# node24-bank.net
KiCad netlist of a schematic drawn in Altium Designer
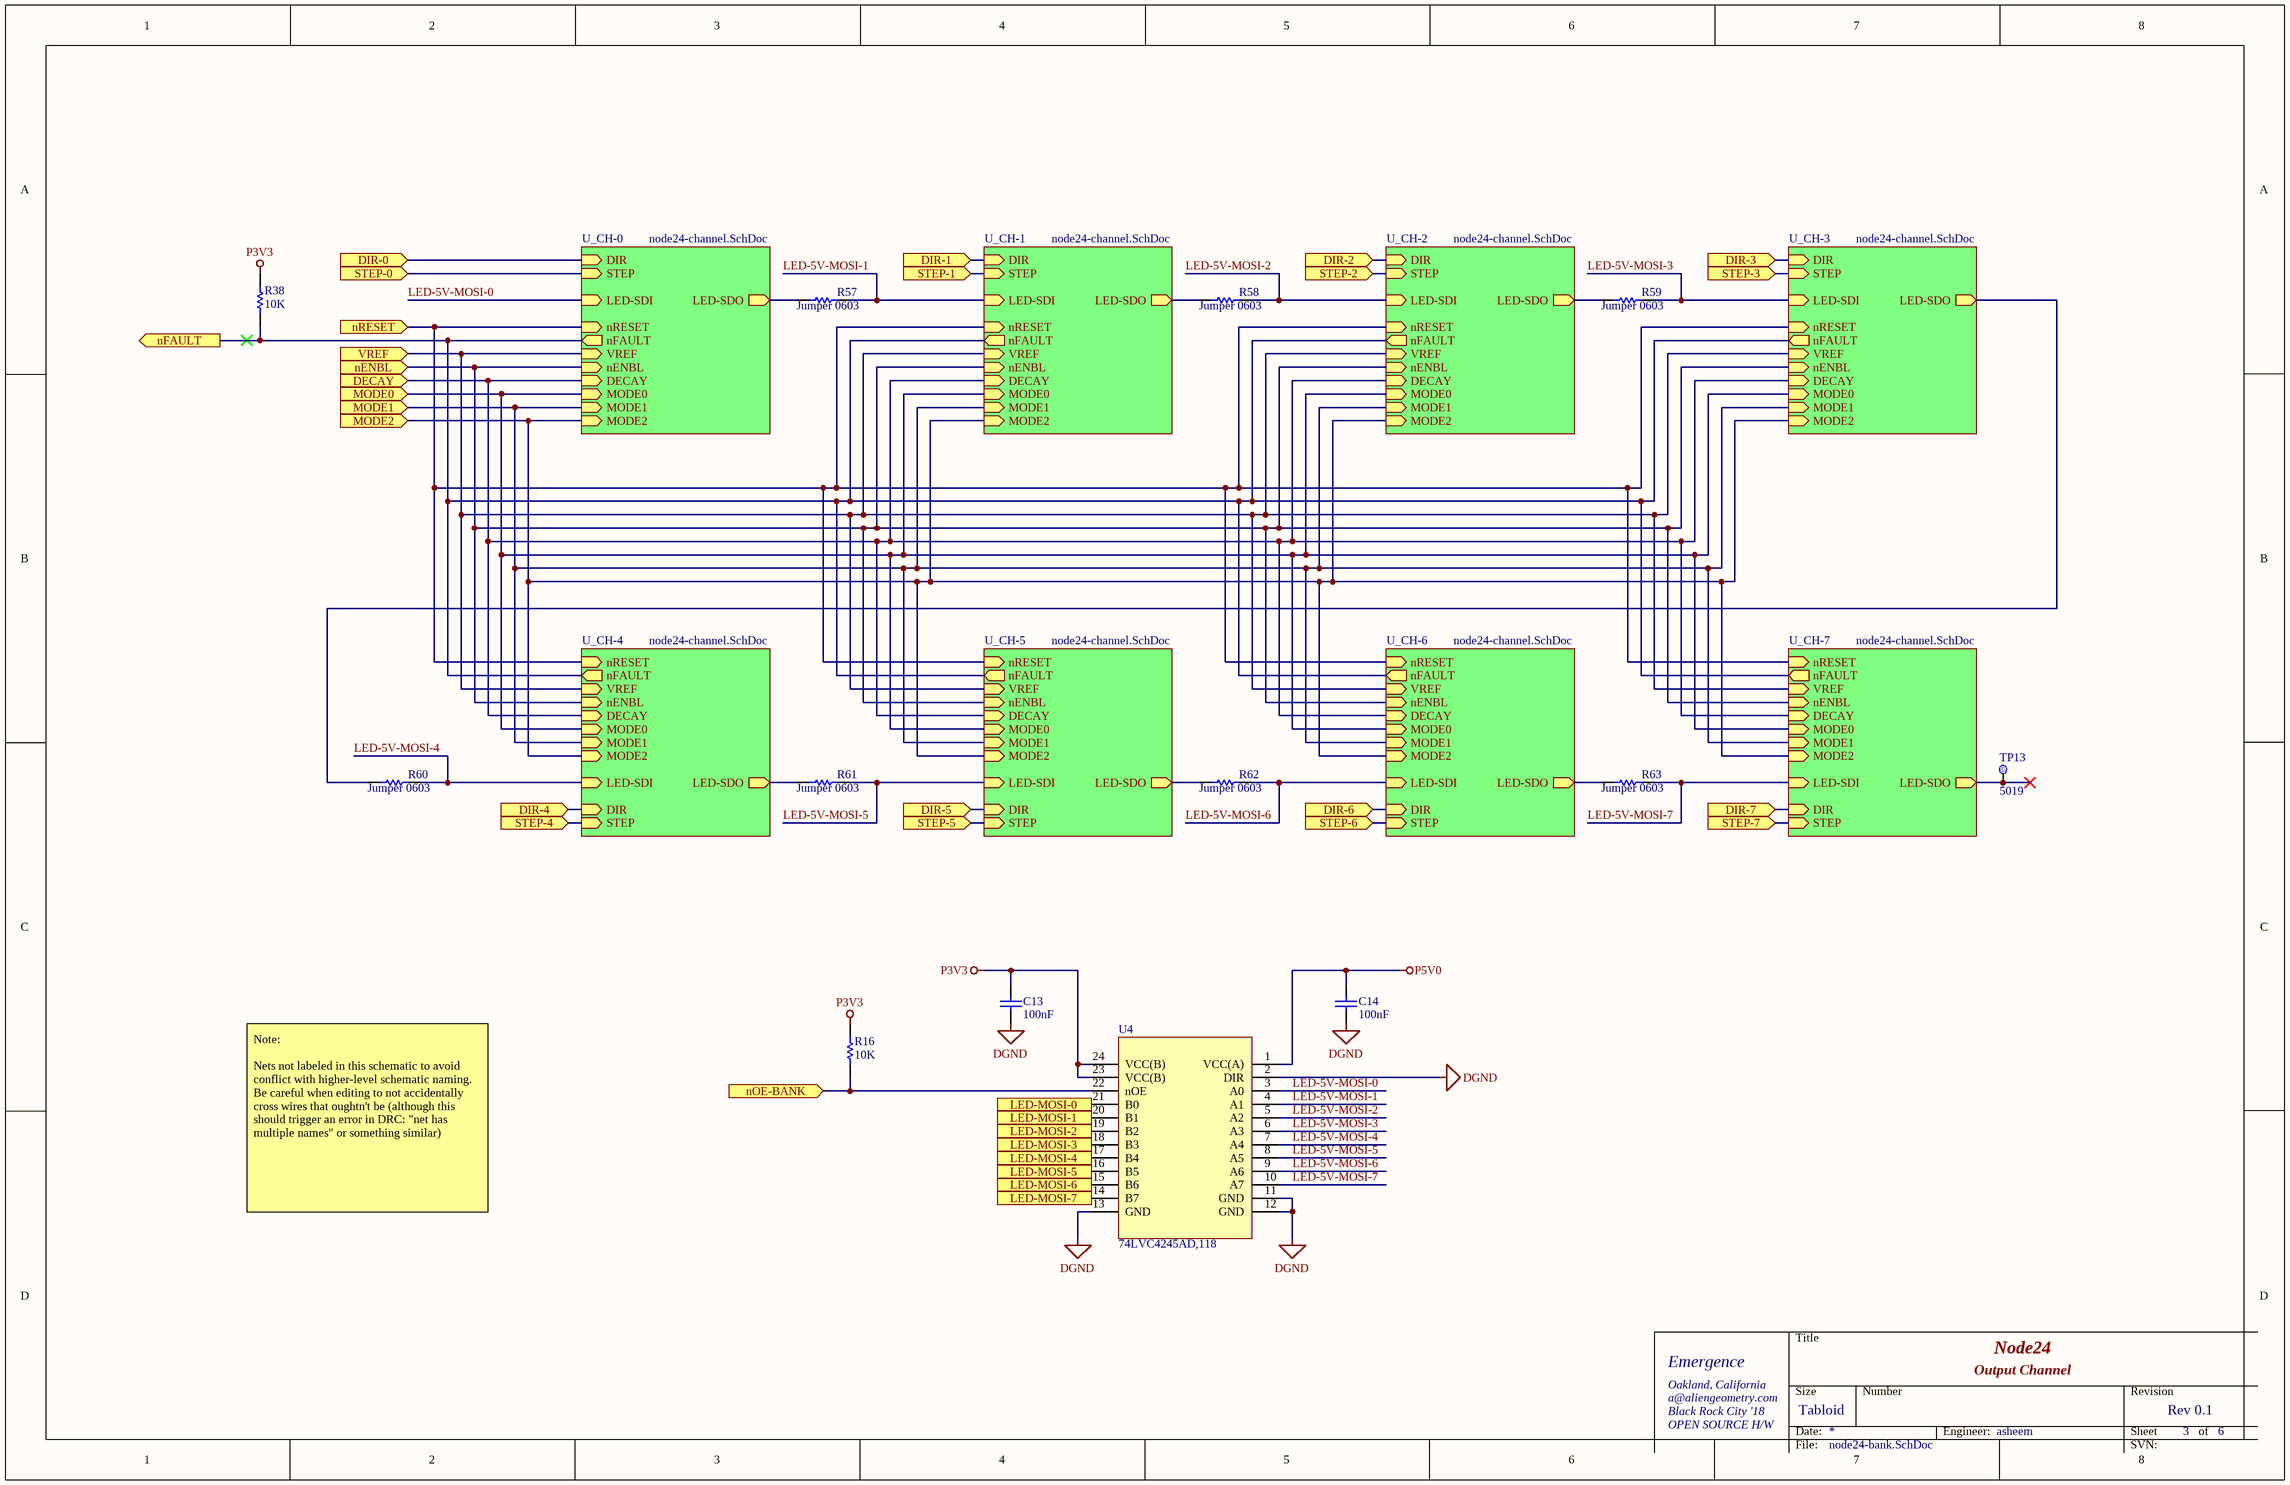
[diagram p0: node24-bank.SchDoc]

(export (version "E")
  (design (tool "Eeschema 10.0.6"))
  (components
    (comp (ref "C13")
      (value "100nF")
      (footprint "CAPC0603(1608)100_L")
      (description "CAP 100nF 50V ±20% 0603 (1608 Metric) Thickness 1mm SMD")
      (fields (field (name "TOLERANCE") "Â±20%"))
      (libsource (lib "Altium Content Vault") (part "CAP"))
    )
    (comp (ref "C14")
      (value "100nF")
      (footprint "CAPC0603(1608)100_L")
      (description "CAP 100nF 50V ±20% 0603 (1608 Metric) Thickness 1mm SMD")
      (fields (field (name "TOLERANCE") "Â±20%"))
      (libsource (lib "Altium Content Vault") (part "CAP"))
    )
    (comp (ref "R16")
      (value "10K")
      (footprint "RESC0603(1608)_L")
      (description "10K 0.1W 1% 0603 (1608 Metric)  SMD")
      (fields (field (name "POWER") "0.1 W") (field (name "TOLERANCE") "1 %"))
      (libsource (lib "Altium Content Vault") (part "RES"))
    )
    (comp (ref "R38")
      (value "10K")
      (footprint "RESC0603(1608)_L")
      (description "10K 0.1W 1% 0603 (1608 Metric)  SMD")
      (fields (field (name "POWER") "0.1 W") (field (name "TOLERANCE") "1 %"))
      (libsource (lib "Altium Content Vault") (part "RES"))
    )
    (comp (ref "R57")
      (value "Jumper 0603")
      (footprint "RESC0603(1608)_L")
      (description "Jumper 0603 (1608 Metric)")
      (fields (field (name "POWER") "None"))
      (libsource (lib "Altium Content Vault") (part "RES"))
    )
    (comp (ref "R58")
      (value "Jumper 0603")
      (footprint "RESC0603(1608)_L")
      (description "Jumper 0603 (1608 Metric)")
      (fields (field (name "POWER") "None"))
      (libsource (lib "Altium Content Vault") (part "RES"))
    )
    (comp (ref "R59")
      (value "Jumper 0603")
      (footprint "RESC0603(1608)_L")
      (description "Jumper 0603 (1608 Metric)")
      (fields (field (name "POWER") "None"))
      (libsource (lib "Altium Content Vault") (part "RES"))
    )
    (comp (ref "R60")
      (value "Jumper 0603")
      (footprint "RESC0603(1608)_L")
      (description "Jumper 0603 (1608 Metric)")
      (fields (field (name "POWER") "None"))
      (libsource (lib "Altium Content Vault") (part "RES"))
    )
    (comp (ref "R61")
      (value "Jumper 0603")
      (footprint "RESC0603(1608)_L")
      (description "Jumper 0603 (1608 Metric)")
      (fields (field (name "POWER") "None"))
      (libsource (lib "Altium Content Vault") (part "RES"))
    )
    (comp (ref "R62")
      (value "Jumper 0603")
      (footprint "RESC0603(1608)_L")
      (description "Jumper 0603 (1608 Metric)")
      (fields (field (name "POWER") "None"))
      (libsource (lib "Altium Content Vault") (part "RES"))
    )
    (comp (ref "R63")
      (value "Jumper 0603")
      (footprint "RESC0603(1608)_L")
      (description "Jumper 0603 (1608 Metric)")
      (fields (field (name "POWER") "None"))
      (libsource (lib "Altium Content Vault") (part "RES"))
    )
    (comp (ref "TP13")
      (value "TEST_POINT_KEYSTONE_5019_SMT")
      (footprint "TEST_POINT_KEYSTONE_5019")
      (description "Circuit Board Hardware - PCB TEST POINT")
      (fields
        (field (name "MANUFACTURER") "Keystone Electronics")
        (field (name "MANUFACTURER PART NUMBER") "5019")
      )
      (libsource (lib "node") (part "TEST_POINT_KEYSTONE_5019_SMT"))
    )
    (comp (ref "U4")
      (value "74LVC4245AD,118")
      (footprint "IC_TSSOP-24")
      (description "IC TRANSCVR TRI-ST DL 24SOIC")
      (fields
        (field (name "MANUFACTURER") "NXP Semiconductors")
        (field (name "MANUFACTURER PART NUMBER") "74LVC4245AD,118")
      )
      (libsource (lib "node") (part "74LVC4245AD,118"))
    )
  )
  (nets
    (net (code "10") (name "/LED-5V-MOSI-0") (class "Default")
      (node (ref "U4") (pin "3") (pinfunction "A0_3") (pintype "passive"))
    )
    (net (code "11") (name "/LED-5V-MOSI-1") (class "Default")
      (node (ref "R57") (pin "2") (pinfunction "2_2") (pintype "passive"))
      (node (ref "U4") (pin "4") (pinfunction "A1_4") (pintype "passive"))
    )
    (net (code "12") (name "/LED-5V-MOSI-2") (class "Default")
      (node (ref "R58") (pin "2") (pinfunction "2_2") (pintype "passive"))
      (node (ref "U4") (pin "5") (pinfunction "A2_5") (pintype "passive"))
    )
    (net (code "13") (name "/LED-5V-MOSI-3") (class "Default")
      (node (ref "R59") (pin "2") (pinfunction "2_2") (pintype "passive"))
      (node (ref "U4") (pin "6") (pinfunction "A3_6") (pintype "passive"))
    )
    (net (code "14") (name "/LED-5V-MOSI-4") (class "Default")
      (node (ref "R60") (pin "2") (pinfunction "2_2") (pintype "passive"))
      (node (ref "U4") (pin "7") (pinfunction "A4_7") (pintype "passive"))
    )
    (net (code "15") (name "/LED-5V-MOSI-5") (class "Default")
      (node (ref "R61") (pin "2") (pinfunction "2_2") (pintype "passive"))
      (node (ref "U4") (pin "8") (pinfunction "A5_8") (pintype "passive"))
    )
    (net (code "16") (name "/LED-5V-MOSI-6") (class "Default")
      (node (ref "R62") (pin "2") (pinfunction "2_2") (pintype "passive"))
      (node (ref "U4") (pin "9") (pinfunction "A6_9") (pintype "passive"))
    )
    (net (code "17") (name "/LED-5V-MOSI-7") (class "Default")
      (node (ref "R63") (pin "2") (pinfunction "2_2") (pintype "passive"))
      (node (ref "U4") (pin "10") (pinfunction "A7_10") (pintype "passive"))
    )
    (net (code "18") (name "/LED-MOSI-0") (class "Default")
      (node (ref "U4") (pin "21") (pinfunction "B0_21") (pintype "passive"))
    )
    (net (code "19") (name "/LED-MOSI-1") (class "Default")
      (node (ref "U4") (pin "20") (pinfunction "B1_20") (pintype "passive"))
    )
    (net (code "20") (name "/LED-MOSI-2") (class "Default")
      (node (ref "U4") (pin "19") (pinfunction "B2_19") (pintype "passive"))
    )
    (net (code "21") (name "/LED-MOSI-3") (class "Default")
      (node (ref "U4") (pin "18") (pinfunction "B3_18") (pintype "passive"))
    )
    (net (code "22") (name "/LED-MOSI-4") (class "Default")
      (node (ref "U4") (pin "17") (pinfunction "B4_17") (pintype "passive"))
    )
    (net (code "23") (name "/LED-MOSI-5") (class "Default")
      (node (ref "U4") (pin "16") (pinfunction "B5_16") (pintype "passive"))
    )
    (net (code "24") (name "/LED-MOSI-6") (class "Default")
      (node (ref "U4") (pin "15") (pinfunction "B6_15") (pintype "passive"))
    )
    (net (code "25") (name "/LED-MOSI-7") (class "Default")
      (node (ref "U4") (pin "14") (pinfunction "B7_14") (pintype "passive"))
    )
    (net (code "26") (name "/LED-SDO") (class "Default")
      (node (ref "R62") (pin "1") (pinfunction "1_1") (pintype "passive"))
    )
    (net (code "27") (name "/LED-SDO_1") (class "Default")
      (node (ref "R63") (pin "1") (pinfunction "1_1") (pintype "passive"))
    )
    (net (code "28") (name "/LED-SDO_2") (class "Default")
      (node (ref "R59") (pin "1") (pinfunction "1_1") (pintype "passive"))
    )
    (net (code "29") (name "/LED-SDO_3") (class "Default")
      (node (ref "R60") (pin "1") (pinfunction "1_1") (pintype "passive"))
    )
    (net (code "30") (name "/LED-SDO_4") (class "Default")
      (node (ref "TP13") (pin "1") (pinfunction "1_1") (pintype "passive+no_connect"))
    )
    (net (code "31") (name "/LED-SDO_5") (class "Default")
      (node (ref "R61") (pin "1") (pinfunction "1_1") (pintype "passive"))
    )
    (net (code "32") (name "/LED-SDO_6") (class "Default")
      (node (ref "R58") (pin "1") (pinfunction "1_1") (pintype "passive"))
    )
    (net (code "33") (name "/LED-SDO_7") (class "Default")
      (node (ref "R57") (pin "1") (pinfunction "1_1") (pintype "passive"))
    )
    (net (code "47") (name "/nFAULT") (class "Default")
      (node (ref "R38") (pin "1") (pinfunction "1_1") (pintype "passive"))
    )
    (net (code "48") (name "/nOE-BANK") (class "Default")
      (node (ref "R16") (pin "1") (pinfunction "1_1") (pintype "passive"))
      (node (ref "U4") (pin "22") (pinfunction "nOE_22") (pintype "passive"))
    )
    (net (code "50") (name "DGND") (class "Default")
      (node (ref "C13") (pin "2") (pinfunction "2_2") (pintype "passive"))
      (node (ref "C14") (pin "2") (pinfunction "2_2") (pintype "passive"))
      (node (ref "U4") (pin "11") (pinfunction "GND_11") (pintype "passive"))
      (node (ref "U4") (pin "12") (pinfunction "GND_12") (pintype "passive"))
      (node (ref "U4") (pin "13") (pinfunction "GND_13") (pintype "passive"))
      (node (ref "U4") (pin "2") (pinfunction "DIR_2") (pintype "passive"))
    )
    (net (code "51") (name "P3V3") (class "Default")
      (node (ref "C13") (pin "1") (pinfunction "1_1") (pintype "passive"))
      (node (ref "R16") (pin "2") (pinfunction "2_2") (pintype "passive"))
      (node (ref "R38") (pin "2") (pinfunction "2_2") (pintype "passive"))
      (node (ref "U4") (pin "23") (pinfunction "VCC(B)_23") (pintype "passive"))
      (node (ref "U4") (pin "24") (pinfunction "VCC(B)_24") (pintype "passive"))
    )
    (net (code "52") (name "P5V0") (class "Default")
      (node (ref "C14") (pin "1") (pinfunction "1_1") (pintype "passive"))
      (node (ref "U4") (pin "1") (pinfunction "VCC(A)_1") (pintype "passive"))
    )
  )
)
